# LM317.net
KiCad netlist of a schematic drawn in Altium Designer
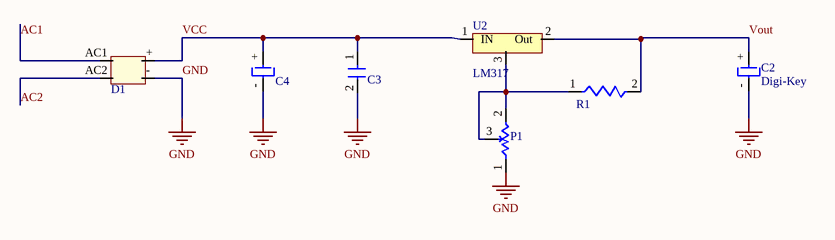
[diagram p0: LM317.SchDoc]

(export (version "E")
  (design (tool "Eeschema 10.0.6"))
  (components
    (comp (ref "C2")
      (value "Digi-Key")
      (footprint "Cap2")
      (description "CAP SUPER 0.22F 2.5V RADIAL")
      (fields
        (field (name "MANUFACTURER") "Eaton Bussmann")
        (field (name "MANUFACTURER PART NUMBER") "B0510-2R5224-R")
      )
      (libsource (lib "EgitimPowerSupply") (part "B0510-2R5224-R"))
    )
    (comp (ref "C3")
      (value "Cap")
      (footprint "Cap1")
      (description "CAP FILM 0.1UF 63VDC RADIAL")
      (fields
        (field (name "MANUFACTURER") "Kemet")
        (field (name "MANUFACTURER PART NUMBER") "R82DC3100DQ50J")
      )
      (libsource (lib "EgitimPowerSupply") (part "R82DC3100DQ50J"))
    )
    (comp (ref "C4")
      (value "2200uF")
      (footprint "CAP3")
      (description "CAP ALUM 2200UF 35V 20% RADIAL")
      (fields
        (field (name "MANUFACTURER") "Panasonic Electronic Components")
        (field (name "MANUFACTURER PART NUMBER") "ECA-1VM222")
      )
      (libsource (lib "EgitimPowerSupply") (part "ECA-1VM222"))
    )
    (comp (ref "D1")
      (value "KoptuDiyot")
      (footprint "2W10")
      (description "RECTIFIER BRIDGE 2A 1000V WOG")
      (fields
        (field (name "MANUFACTURER") "Vishay Semiconductor Diodes Division")
        (field (name "MANUFACTURER PART NUMBER") "2W10G-E4/51")
      )
      (libsource (lib "EgitimPowerSupply") (part "2W10G-E4/51"))
    )
    (comp (ref "P1")
      (value "Pot")
      (footprint "Pot")
      (description "POT 10K OHM 9MM SQ RTANG PLAST")
      (fields
        (field (name "MANUFACTURER") "Bourns Inc.")
        (field (name "MANUFACTURER PART NUMBER") "3310C-001-103L")
      )
      (libsource (lib "EgitimPowerSupply") (part "3310C-001-103L"))
    )
    (comp (ref "R1")
      (value "Res")
      (footprint "R1")
      (description "RES 10K OHM 1/4W 5% CARBON FILM")
      (fields
        (field (name "MANUFACTURER") "Stackpole Electronics Inc")
        (field (name "MANUFACTURER PART NUMBER") "CF14JT10K0")
      )
      (libsource (lib "EgitimPowerSupply") (part "CF14JT10K0"))
    )
    (comp (ref "U2")
      (value "LM317")
      (footprint "TO220")
      (description "Linear Voltage Regulators 1.5A ADJ 1.2-37V Positive")
      (fields
        (field (name "MANUFACTURER") "ON Semiconductor")
        (field (name "MANUFACTURER PART NUMBER") "LM317TG")
      )
      (libsource (lib "EgitimPowerSupply") (part "LM317TG"))
    )
  )
  (nets
    (net (code "1") (name "/AC1") (class "Default")
      (node (ref "D1") (pin "AC1") (pinfunction "AC1_AC1") (pintype "passive"))
    )
    (net (code "2") (name "/AC2") (class "Default")
      (node (ref "D1") (pin "AC2") (pinfunction "AC2_AC2") (pintype "passive"))
    )
    (net (code "3") (name "/VCC") (class "Default")
      (node (ref "C3") (pin "1") (pinfunction "1_1") (pintype "passive"))
      (node (ref "C4") (pin "+") (pinfunction "+_+") (pintype "passive"))
      (node (ref "D1") (pin "+") (pinfunction "+_+") (pintype "passive"))
      (node (ref "U2") (pin "1") (pinfunction "IN_1") (pintype "passive"))
    )
    (net (code "4") (name "/Vout") (class "Default")
      (node (ref "C2") (pin "+") (pinfunction "+_+") (pintype "passive"))
      (node (ref "R1") (pin "2") (pinfunction "2_2") (pintype "passive"))
      (node (ref "U2") (pin "2") (pinfunction "Out_2") (pintype "passive"))
    )
    (net (code "5") (name "GND") (class "Default")
      (node (ref "C2") (pin "-") (pinfunction "-_-") (pintype "passive"))
      (node (ref "C3") (pin "2") (pinfunction "2_2") (pintype "passive"))
      (node (ref "C4") (pin "-") (pinfunction "-_-") (pintype "passive"))
      (node (ref "D1") (pin "-") (pinfunction "-_-") (pintype "passive"))
      (node (ref "P1") (pin "1") (pinfunction "1_1") (pintype "passive"))
    )
    (net (code "6") (name "Net-(P1-Pad2)") (class "Default")
      (node (ref "P1") (pin "2") (pinfunction "2_2") (pintype "passive"))
      (node (ref "P1") (pin "3") (pinfunction "3_3") (pintype "passive"))
      (node (ref "R1") (pin "1") (pinfunction "1_1") (pintype "passive"))
      (node (ref "U2") (pin "3") (pinfunction "3_3") (pintype "passive"))
    )
  )
)
